# Esquem_tico.net
KiCad netlist of a schematic drawn in EAGLE
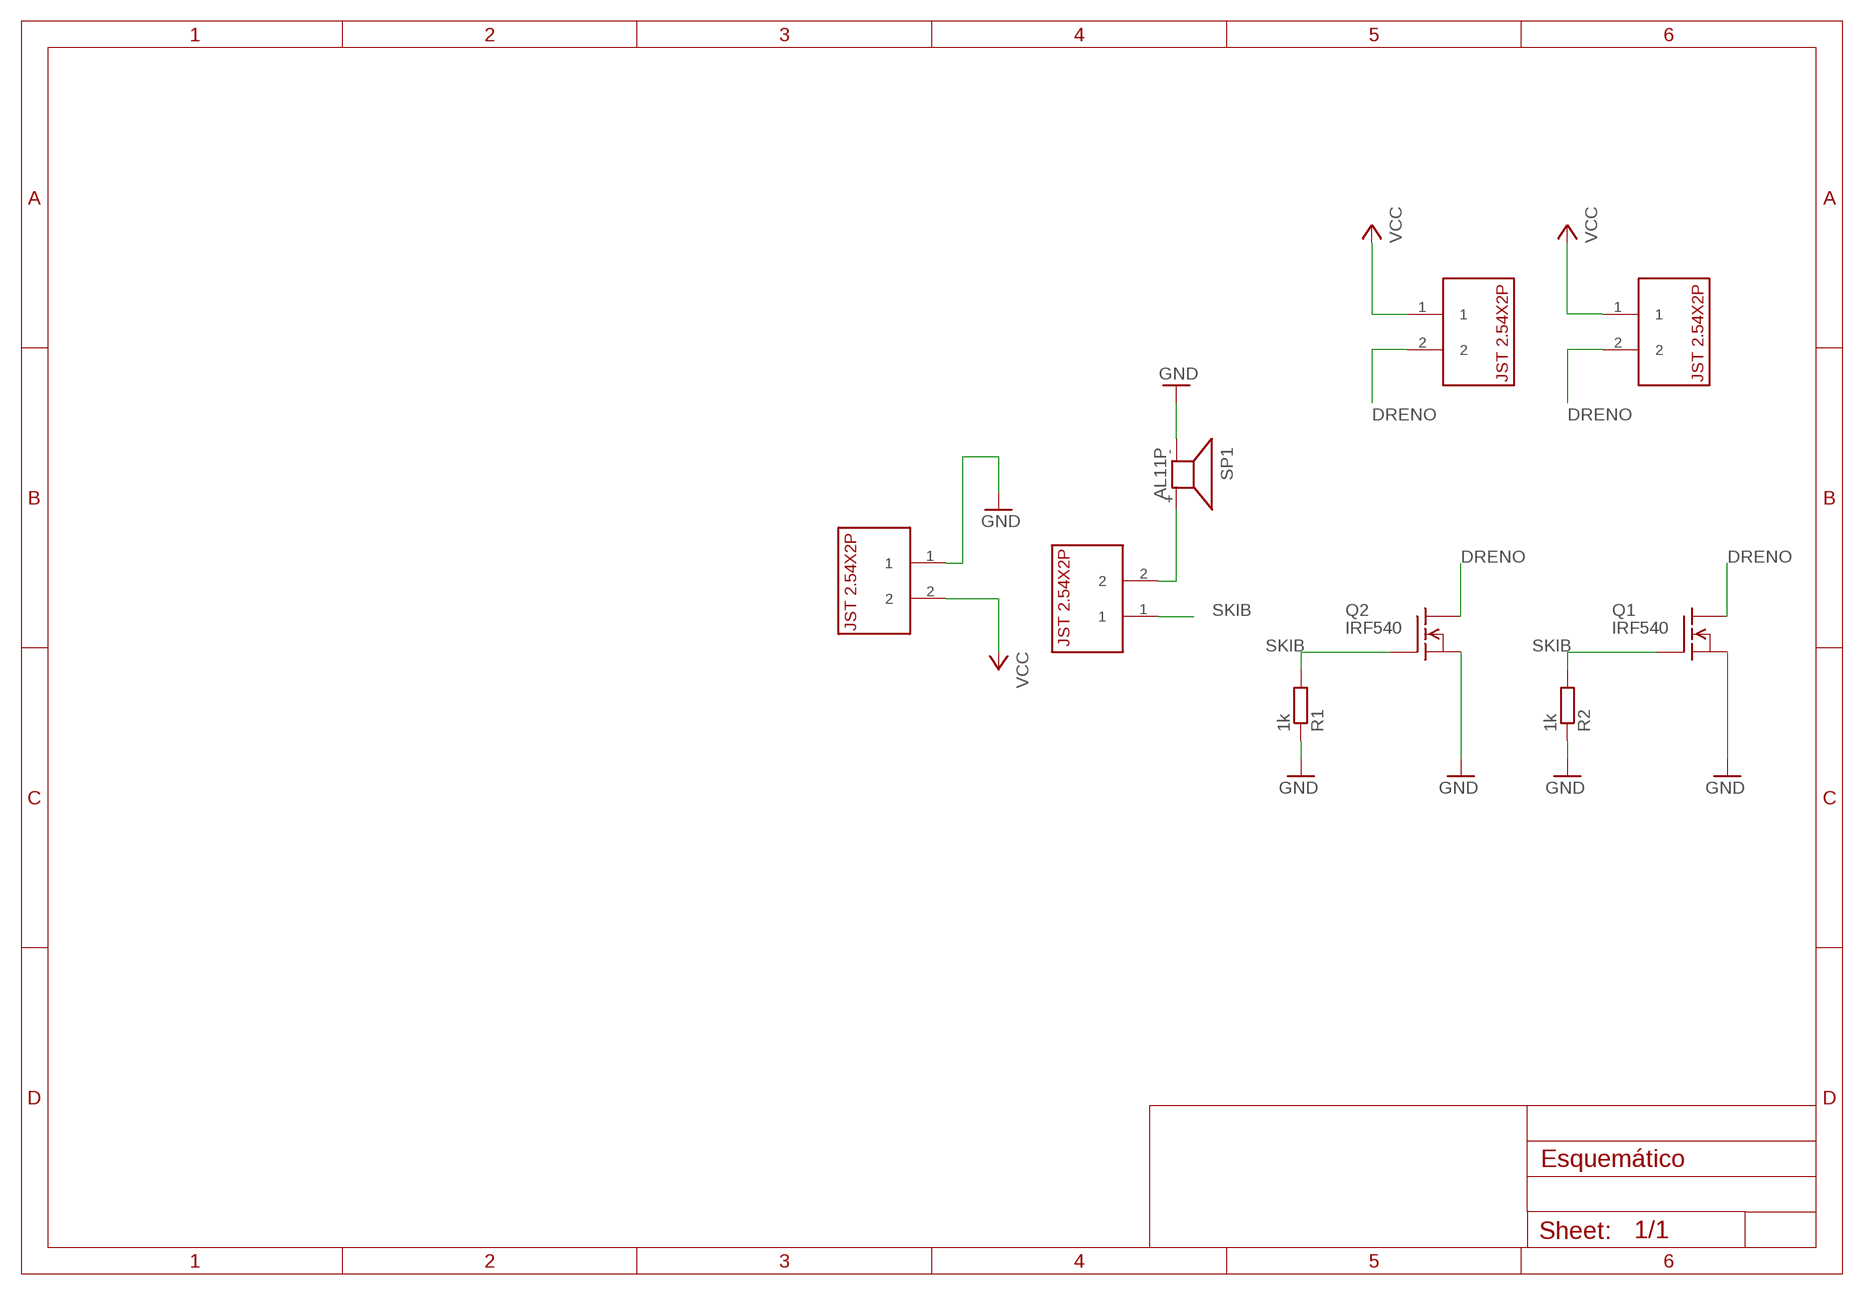
[diagram p0: schematic, sheet 1]

(export (version "E")
  (design (tool "Eeschema 10.0.6"))
  (components
    (comp (ref "Q1")
      (value "IRF540")
      (footprint "eagle-import:TO220")
      (libsource (lib "eagle-import") (part "IRF540"))
    )
    (comp (ref "Q2")
      (value "IRF540")
      (footprint "eagle-import:TO220")
      (libsource (lib "eagle-import") (part "IRF540"))
    )
    (comp (ref "R1")
      (value "1k")
      (footprint "eagle-import:0204_7")
      (libsource (lib "eagle-import") (part "R-EU_0204/7"))
    )
    (comp (ref "R2")
      (value "1k")
      (footprint "eagle-import:0204_7")
      (libsource (lib "eagle-import") (part "R-EU_0204/7"))
    )
    (comp (ref "SP1")
      (value "AL11P")
      (footprint "eagle-import:AL11P")
      (libsource (lib "eagle-import") (part "AL11P"))
    )
    (comp (ref "U$1")
      (value "JST2.54X2P")
      (footprint "eagle-import:JST2.54X2P_FOOTPRINT")
      (libsource (lib "eagle-import") (part "JST2.54X2P"))
    )
    (comp (ref "U$2")
      (value "JST2.54X2P")
      (footprint "eagle-import:JST2.54X2P_FOOTPRINT")
      (libsource (lib "eagle-import") (part "JST2.54X2P"))
    )
    (comp (ref "U$3")
      (value "JST2.54X2P")
      (footprint "eagle-import:JST2.54X2P_FOOTPRINT")
      (libsource (lib "eagle-import") (part "JST2.54X2P"))
    )
    (comp (ref "U$4")
      (value "JST2.54X2P")
      (footprint "eagle-import:JST2.54X2P_FOOTPRINT")
      (libsource (lib "eagle-import") (part "JST2.54X2P"))
    )
  )
  (nets
    (net (code "1") (name "/DRENO") (class "Default")
      (node (ref "Q1") (pin "2") (pinfunction "D_2") (pintype "passive"))
      (node (ref "Q2") (pin "2") (pinfunction "D_2") (pintype "passive"))
      (node (ref "U$2") (pin "2") (pinfunction "2_2") (pintype "bidirectional"))
      (node (ref "U$3") (pin "2") (pinfunction "2_2") (pintype "bidirectional"))
    )
    (net (code "2") (name "/SKIB") (class "Default")
      (node (ref "Q1") (pin "1") (pinfunction "G_1") (pintype "passive"))
      (node (ref "Q2") (pin "1") (pinfunction "G_1") (pintype "passive"))
      (node (ref "R1") (pin "2") (pinfunction "2_2") (pintype "passive"))
      (node (ref "R2") (pin "2") (pinfunction "2_2") (pintype "passive"))
      (node (ref "U$1") (pin "1") (pinfunction "1_1") (pintype "bidirectional"))
    )
    (net (code "3") (name "GND") (class "Default")
      (node (ref "Q1") (pin "3") (pinfunction "S_3") (pintype "passive"))
      (node (ref "Q2") (pin "3") (pinfunction "S_3") (pintype "passive"))
      (node (ref "R1") (pin "1") (pinfunction "1_1") (pintype "passive"))
      (node (ref "R2") (pin "1") (pinfunction "1_1") (pintype "passive"))
      (node (ref "SP1") (pin "-") (pinfunction "1_-") (pintype "passive"))
      (node (ref "U$4") (pin "1") (pinfunction "1_1") (pintype "bidirectional"))
    )
    (net (code "4") (name "Net-(SP1-2)") (class "Default")
      (node (ref "SP1") (pin "+") (pinfunction "2_+") (pintype "passive"))
      (node (ref "U$1") (pin "2") (pinfunction "2_2") (pintype "bidirectional"))
    )
    (net (code "5") (name "VCC") (class "Default")
      (node (ref "U$2") (pin "1") (pinfunction "1_1") (pintype "bidirectional"))
      (node (ref "U$3") (pin "1") (pinfunction "1_1") (pintype "bidirectional"))
      (node (ref "U$4") (pin "2") (pinfunction "2_2") (pintype "bidirectional"))
    )
  )
)
